# MeteoV4_0.net
KiCad netlist of a schematic drawn in EAGLE
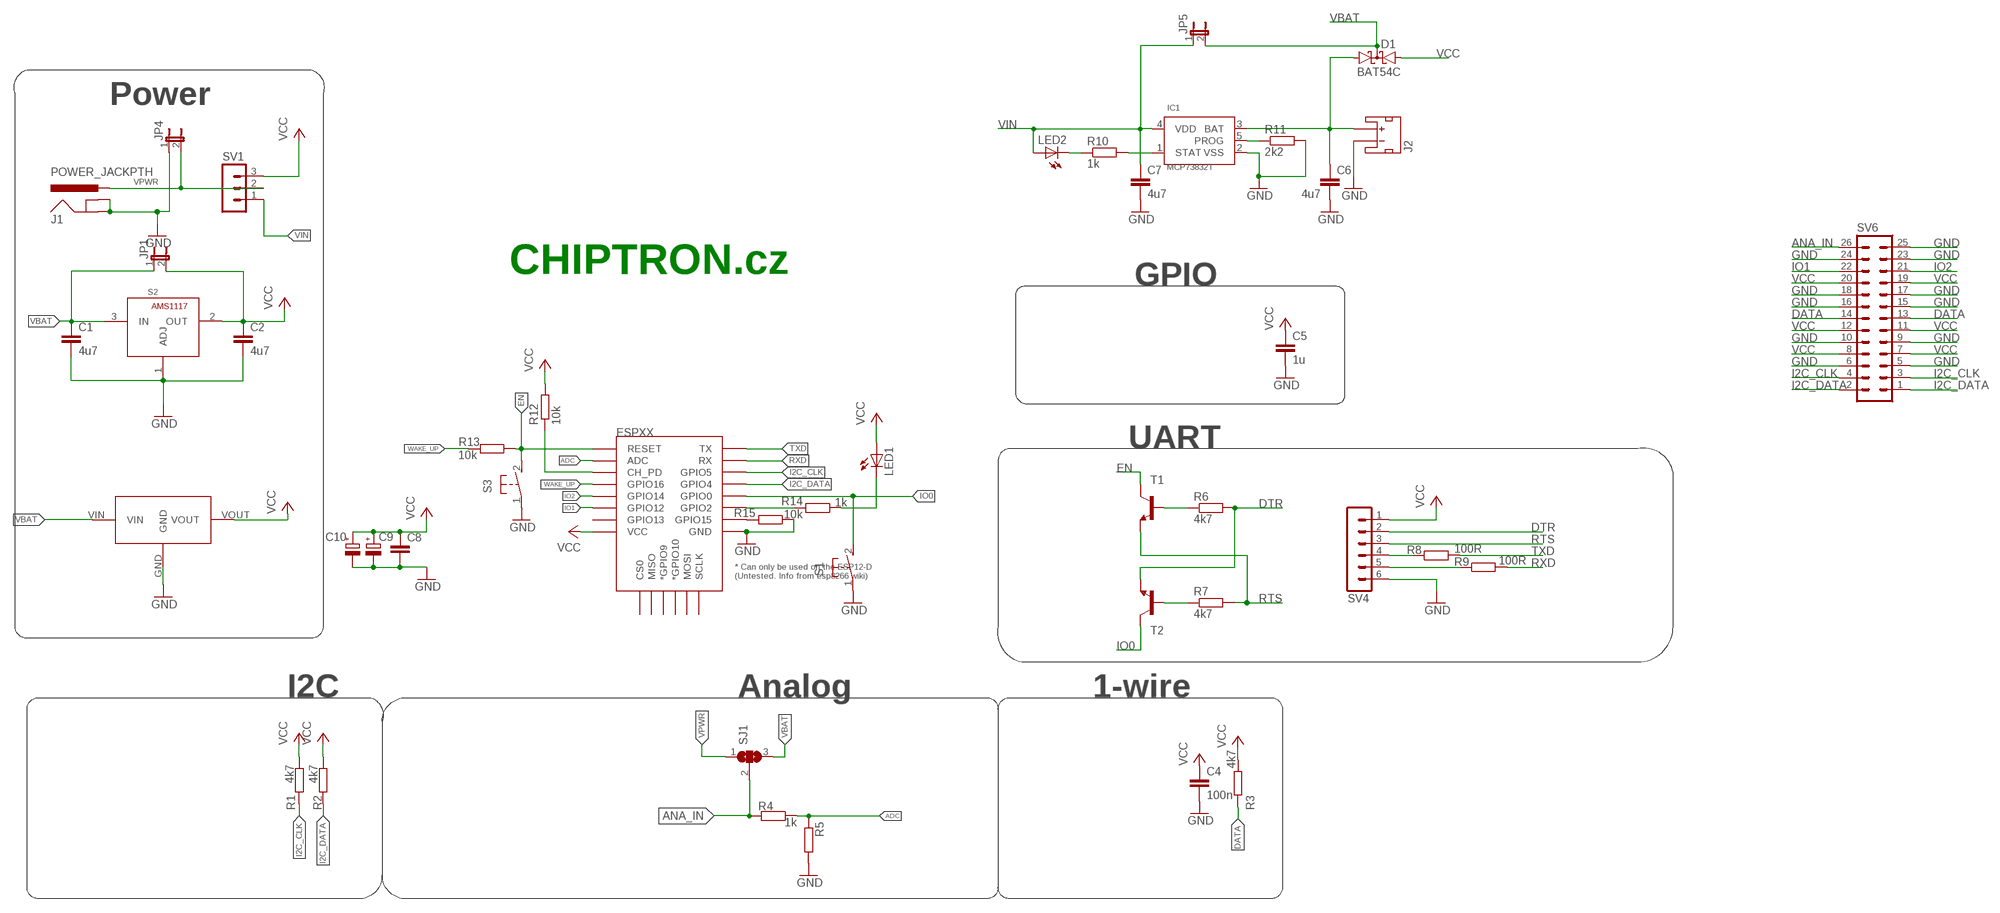
[diagram p0: schematic, sheet 1]

(export (version "E")
  (design (tool "Eeschema 10.0.6"))
  (components
    (comp (ref "C1")
      (value "4u7")
      (footprint "eagle-import:C0805")
      (libsource (lib "eagle-import") (part "C-EUC0805"))
    )
    (comp (ref "C2")
      (value "4u7")
      (footprint "eagle-import:C0805")
      (libsource (lib "eagle-import") (part "C-EUC0805"))
    )
    (comp (ref "C4")
      (value "100n")
      (footprint "eagle-import:C0805")
      (libsource (lib "eagle-import") (part "C-EUC0805"))
    )
    (comp (ref "C5")
      (value "1u")
      (footprint "eagle-import:C0805")
      (libsource (lib "eagle-import") (part "C-EUC0805"))
    )
    (comp (ref "C6")
      (value "4u7")
      (footprint "eagle-import:C0805")
      (libsource (lib "eagle-import") (part "C-EUC0805"))
    )
    (comp (ref "C7")
      (value "4u7")
      (footprint "eagle-import:C0805")
      (libsource (lib "eagle-import") (part "C-EUC0805"))
    )
    (comp (ref "C8")
      (value "C-EUC0805")
      (footprint "eagle-import:C0805")
      (libsource (lib "eagle-import") (part "C-EUC0805"))
    )
    (comp (ref "C9")
      (value "CPOL-EUSMCB")
      (footprint "eagle-import:SMC_B")
      (libsource (lib "eagle-import") (part "CPOL-EUSMCB"))
    )
    (comp (ref "C10")
      (value "CPOL-EUSMCC")
      (footprint "eagle-import:SMC_C")
      (libsource (lib "eagle-import") (part "CPOL-EUSMCC"))
    )
    (comp (ref "D1")
      (value "BAT54C")
      (footprint "eagle-import:SOT23")
      (libsource (lib "eagle-import") (part "BAT54C"))
    )
    (comp (ref "ESPXX")
      (value "ESP12ESMD")
      (footprint "eagle-import:ESP12E-SMD")
      (libsource (lib "eagle-import") (part "ESP12ESMD"))
    )
    (comp (ref "IC1")
      (value "MCP73832T")
      (footprint "eagle-import:SOT23-5")
      (libsource (lib "eagle-import") (part "MCP73832T"))
    )
    (comp (ref "J1")
      (value "POWER_JACKPTH")
      (footprint "eagle-import:POWER_JACK_PTH")
      (libsource (lib "eagle-import") (part "POWER_JACKPTH"))
    )
    (comp (ref "J2")
      (value "JST_2MM_MALE")
      (footprint "eagle-import:JST-2-SMD")
      (libsource (lib "eagle-import") (part "JST_2MM_MALE"))
    )
    (comp (ref "JP1")
      (value "JP1E")
      (footprint "eagle-import:JP1")
      (libsource (lib "eagle-import") (part "JP1E"))
    )
    (comp (ref "JP4")
      (value "JP1E")
      (footprint "eagle-import:JP1")
      (libsource (lib "eagle-import") (part "JP1E"))
    )
    (comp (ref "JP5")
      (value "JP1E")
      (footprint "eagle-import:JP1")
      (libsource (lib "eagle-import") (part "JP1E"))
    )
    (comp (ref "LED1")
      (value "LEDCHIP-LED0805")
      (footprint "eagle-import:CHIP-LED0805")
      (libsource (lib "eagle-import") (part "LEDCHIP-LED0805"))
    )
    (comp (ref "LED2")
      (value "LEDCHIP-LED0805")
      (footprint "eagle-import:CHIP-LED0805")
      (libsource (lib "eagle-import") (part "LEDCHIP-LED0805"))
    )
    (comp (ref "R1")
      (value "4k7")
      (footprint "eagle-import:M0805")
      (libsource (lib "eagle-import") (part "R-EU_M0805"))
    )
    (comp (ref "R2")
      (value "4k7")
      (footprint "eagle-import:M0805")
      (libsource (lib "eagle-import") (part "R-EU_M0805"))
    )
    (comp (ref "R3")
      (value "4k7")
      (footprint "eagle-import:M0805")
      (libsource (lib "eagle-import") (part "R-EU_M0805"))
    )
    (comp (ref "R4")
      (value "1k")
      (footprint "eagle-import:M0805")
      (libsource (lib "eagle-import") (part "R-EU_M0805"))
    )
    (comp (ref "R5")
      (value "R-EU_M0805")
      (footprint "eagle-import:M0805")
      (libsource (lib "eagle-import") (part "R-EU_M0805"))
    )
    (comp (ref "R6")
      (value "4k7")
      (footprint "eagle-import:M0805")
      (libsource (lib "eagle-import") (part "R-EU_M0805"))
    )
    (comp (ref "R7")
      (value "4k7")
      (footprint "eagle-import:M0805")
      (libsource (lib "eagle-import") (part "R-EU_M0805"))
    )
    (comp (ref "R8")
      (value "100R")
      (footprint "eagle-import:M0805")
      (libsource (lib "eagle-import") (part "R-EU_M0805"))
    )
    (comp (ref "R9")
      (value "100R")
      (footprint "eagle-import:M0805")
      (libsource (lib "eagle-import") (part "R-EU_M0805"))
    )
    (comp (ref "R10")
      (value "1k")
      (footprint "eagle-import:M0805")
      (libsource (lib "eagle-import") (part "R-EU_M0805"))
    )
    (comp (ref "R11")
      (value "2k2")
      (footprint "eagle-import:M0805")
      (libsource (lib "eagle-import") (part "R-EU_M0805"))
    )
    (comp (ref "R12")
      (value "10k")
      (footprint "eagle-import:M0805")
      (libsource (lib "eagle-import") (part "R-EU_M0805"))
    )
    (comp (ref "R13")
      (value "10k")
      (footprint "eagle-import:M0805")
      (libsource (lib "eagle-import") (part "R-EU_M0805"))
    )
    (comp (ref "R14")
      (value "1k")
      (footprint "eagle-import:M0805")
      (libsource (lib "eagle-import") (part "R-EU_M0805"))
    )
    (comp (ref "R15")
      (value "10k")
      (footprint "eagle-import:M0805")
      (libsource (lib "eagle-import") (part "R-EU_M0805"))
    )
    (comp (ref "S1")
      (value "31-XX")
      (footprint "eagle-import:B3F-31XX")
      (fields (field (name "MPN") "B3F-3100"))
      (libsource (lib "eagle-import") (part "31-XX"))
    )
    (comp (ref "S2")
      (value "AMS1117")
      (footprint "eagle-import:SOT-223-3")
      (libsource (lib "eagle-import") (part "AMS1117"))
    )
    (comp (ref "S3")
      (value "31-XX")
      (footprint "eagle-import:B3F-31XX")
      (fields (field (name "MPN") "B3F-3100"))
      (libsource (lib "eagle-import") (part "31-XX"))
    )
    (comp (ref "SJ1")
      (value "SJ2W")
      (footprint "eagle-import:SJ_2")
      (libsource (lib "eagle-import") (part "SJ2W"))
    )
    (comp (ref "SV1")
      (value "MA03-1")
      (footprint "eagle-import:MA03-1")
      (libsource (lib "eagle-import") (part "MA03-1"))
    )
    (comp (ref "SV4")
      (value "MA06-1")
      (footprint "eagle-import:MA06-1")
      (libsource (lib "eagle-import") (part "MA06-1"))
    )
    (comp (ref "SV6")
      (value "MA13-2")
      (footprint "eagle-import:MA13-2")
      (libsource (lib "eagle-import") (part "MA13-2"))
    )
    (comp (ref "T1")
      (value "BC846-NPN-SOT23-BEC")
      (footprint "eagle-import:SOT23-BEC")
      (libsource (lib "eagle-import") (part "-NPN-SOT23-BECBC846"))
    )
    (comp (ref "T2")
      (value "BC846-NPN-SOT23-BEC")
      (footprint "eagle-import:SOT23-BEC")
      (libsource (lib "eagle-import") (part "-NPN-SOT23-BECBC846"))
    )
    (comp (ref "U$1")
      (value "HT7333")
      (footprint "eagle-import:SOT89")
      (libsource (lib "eagle-import") (part "HT7333"))
    )
  )
  (nets
    (net (code "1") (name "/DTR") (class "Default")
      (node (ref "R6") (pin "2") (pinfunction "2_2") (pintype "passive"))
      (node (ref "SV4") (pin "2") (pinfunction "2_2") (pintype "passive"))
      (node (ref "T2") (pin "E") (pinfunction "E_E") (pintype "passive"))
    )
    (net (code "2") (name "/RTS") (class "Default")
      (node (ref "R7") (pin "2") (pinfunction "2_2") (pintype "passive"))
      (node (ref "SV4") (pin "3") (pinfunction "3_3") (pintype "passive"))
      (node (ref "T1") (pin "E") (pinfunction "E_E") (pintype "passive"))
    )
    (net (code "3") (name "ADC") (class "Default")
      (node (ref "ESPXX") (pin "ADC") (pinfunction "ADC_ADC") (pintype "bidirectional"))
      (node (ref "R4") (pin "1") (pinfunction "1_1") (pintype "passive"))
      (node (ref "R5") (pin "1") (pinfunction "1_1") (pintype "passive"))
    )
    (net (code "4") (name "ANA_IN") (class "Default")
      (node (ref "R4") (pin "2") (pinfunction "2_2") (pintype "passive"))
      (node (ref "SJ1") (pin "2") (pinfunction "2_2") (pintype "passive"))
      (node (ref "SV6") (pin "26") (pinfunction "26_26") (pintype "passive"))
    )
    (net (code "5") (name "DATA") (class "Default")
      (node (ref "R3") (pin "1") (pinfunction "1_1") (pintype "passive"))
      (node (ref "SV6") (pin "13") (pinfunction "13_13") (pintype "passive"))
      (node (ref "SV6") (pin "14") (pinfunction "14_14") (pintype "passive"))
    )
    (net (code "6") (name "EN") (class "Default")
      (node (ref "ESPXX") (pin "RESET") (pinfunction "RESET_RESET") (pintype "bidirectional"))
      (node (ref "R13") (pin "1") (pinfunction "1_1") (pintype "passive"))
      (node (ref "S3") (pin "2") (pinfunction "S_2") (pintype "passive"))
      (node (ref "T1") (pin "C") (pinfunction "C_C") (pintype "passive"))
    )
    (net (code "7") (name "GND") (class "Default")
      (node (ref "C1") (pin "2") (pinfunction "2_2") (pintype "passive"))
      (node (ref "C10") (pin "-") (pinfunction "-_-") (pintype "passive"))
      (node (ref "C2") (pin "2") (pinfunction "2_2") (pintype "passive"))
      (node (ref "C4") (pin "2") (pinfunction "2_2") (pintype "passive"))
      (node (ref "C5") (pin "2") (pinfunction "2_2") (pintype "passive"))
      (node (ref "C6") (pin "2") (pinfunction "2_2") (pintype "passive"))
      (node (ref "C7") (pin "2") (pinfunction "2_2") (pintype "passive"))
      (node (ref "C8") (pin "2") (pinfunction "2_2") (pintype "passive"))
      (node (ref "C9") (pin "-") (pinfunction "-_-") (pintype "passive"))
      (node (ref "ESPXX") (pin "GND") (pinfunction "GND_GND") (pintype "bidirectional"))
      (node (ref "IC1") (pin "2") (pinfunction "VSS_2") (pintype "bidirectional"))
      (node (ref "J1") (pin "GND") (pinfunction "GND_GND") (pintype "bidirectional"))
      (node (ref "J1") (pin "GNDBREAK") (pinfunction "GNDBREAK_GNDBREAK") (pintype "bidirectional"))
      (node (ref "J2") (pin "1") (pinfunction "-_1") (pintype "bidirectional"))
      (node (ref "JP4") (pin "1") (pinfunction "1_1") (pintype "passive"))
      (node (ref "R11") (pin "2") (pinfunction "2_2") (pintype "passive"))
      (node (ref "R15") (pin "1") (pinfunction "1_1") (pintype "passive"))
      (node (ref "R5") (pin "2") (pinfunction "2_2") (pintype "passive"))
      (node (ref "S1") (pin "1") (pinfunction "P_1") (pintype "passive"))
      (node (ref "S2") (pin "1") (pinfunction "ADJ_1") (pintype "bidirectional"))
      (node (ref "S3") (pin "1") (pinfunction "P_1") (pintype "passive"))
      (node (ref "SV4") (pin "6") (pinfunction "6_6") (pintype "passive"))
      (node (ref "SV6") (pin "10") (pinfunction "10_10") (pintype "passive"))
      (node (ref "SV6") (pin "15") (pinfunction "15_15") (pintype "passive"))
      (node (ref "SV6") (pin "16") (pinfunction "16_16") (pintype "passive"))
      (node (ref "SV6") (pin "17") (pinfunction "17_17") (pintype "passive"))
      (node (ref "SV6") (pin "18") (pinfunction "18_18") (pintype "passive"))
      (node (ref "SV6") (pin "23") (pinfunction "23_23") (pintype "passive"))
      (node (ref "SV6") (pin "24") (pinfunction "24_24") (pintype "passive"))
      (node (ref "SV6") (pin "25") (pinfunction "25_25") (pintype "passive"))
      (node (ref "SV6") (pin "5") (pinfunction "5_5") (pintype "passive"))
      (node (ref "SV6") (pin "6") (pinfunction "6_6") (pintype "passive"))
      (node (ref "SV6") (pin "9") (pinfunction "9_9") (pintype "passive"))
      (node (ref "U$1") (pin "GND") (pinfunction "GND_GND") (pintype "bidirectional"))
    )
    (net (code "8") (name "I2C_CLK") (class "Default")
      (node (ref "ESPXX") (pin "GPIO5") (pinfunction "GPIO5_GPIO5") (pintype "bidirectional"))
      (node (ref "R1") (pin "1") (pinfunction "1_1") (pintype "passive"))
      (node (ref "SV6") (pin "3") (pinfunction "3_3") (pintype "passive"))
      (node (ref "SV6") (pin "4") (pinfunction "4_4") (pintype "passive"))
    )
    (net (code "9") (name "I2C_DATA") (class "Default")
      (node (ref "ESPXX") (pin "GPIO4") (pinfunction "GPIO4_GPIO4") (pintype "bidirectional"))
      (node (ref "R2") (pin "1") (pinfunction "1_1") (pintype "passive"))
      (node (ref "SV6") (pin "1") (pinfunction "1_1") (pintype "passive"))
      (node (ref "SV6") (pin "2") (pinfunction "2_2") (pintype "passive"))
    )
    (net (code "10") (name "IO0") (class "Default")
      (node (ref "ESPXX") (pin "GPIO0") (pinfunction "GPIO0_GPIO0") (pintype "bidirectional"))
      (node (ref "S1") (pin "2") (pinfunction "S_2") (pintype "passive"))
      (node (ref "T2") (pin "C") (pinfunction "C_C") (pintype "passive"))
    )
    (net (code "11") (name "IO1") (class "Default")
      (node (ref "ESPXX") (pin "GPIO12") (pinfunction "GPIO12_GPIO12") (pintype "bidirectional"))
      (node (ref "SV6") (pin "22") (pinfunction "22_22") (pintype "passive"))
    )
    (net (code "12") (name "IO2") (class "Default")
      (node (ref "ESPXX") (pin "GPIO14") (pinfunction "GPIO14_GPIO14") (pintype "bidirectional"))
      (node (ref "SV6") (pin "21") (pinfunction "21_21") (pintype "passive"))
    )
    (net (code "13") (name "Net-(D1-A1)") (class "Default")
      (node (ref "C6") (pin "1") (pinfunction "1_1") (pintype "passive"))
      (node (ref "D1") (pin "1") (pinfunction "A1_1") (pintype "passive"))
      (node (ref "IC1") (pin "3") (pinfunction "BAT_3") (pintype "bidirectional"))
      (node (ref "J2") (pin "2") (pinfunction "+_2") (pintype "bidirectional"))
    )
    (net (code "14") (name "Net-(ESPXX-PadCH_PD)") (class "Default")
      (node (ref "ESPXX") (pin "CH_PD") (pinfunction "CH_PD_CH_PD") (pintype "bidirectional"))
      (node (ref "R12") (pin "1") (pinfunction "1_1") (pintype "passive"))
    )
    (net (code "15") (name "Net-(ESPXX-PadGPIO2)") (class "Default")
      (node (ref "ESPXX") (pin "GPIO2") (pinfunction "GPIO2_GPIO2") (pintype "bidirectional"))
      (node (ref "R14") (pin "2") (pinfunction "2_2") (pintype "passive"))
    )
    (net (code "16") (name "Net-(ESPXX-PadGPIO15)") (class "Default")
      (node (ref "ESPXX") (pin "GPIO15") (pinfunction "GPIO15_GPIO15") (pintype "bidirectional"))
      (node (ref "R15") (pin "2") (pinfunction "2_2") (pintype "passive"))
    )
    (net (code "17") (name "Net-(IC1-PROG)") (class "Default")
      (node (ref "IC1") (pin "5") (pinfunction "PROG_5") (pintype "bidirectional"))
      (node (ref "R11") (pin "1") (pinfunction "1_1") (pintype "passive"))
    )
    (net (code "18") (name "Net-(IC1-STAT)") (class "Default")
      (node (ref "IC1") (pin "1") (pinfunction "STAT_1") (pintype "bidirectional"))
      (node (ref "R10") (pin "2") (pinfunction "2_2") (pintype "passive"))
    )
    (net (code "19") (name "Net-(LED1-PadC)") (class "Default")
      (node (ref "LED1") (pin "C") (pinfunction "C_C") (pintype "passive"))
      (node (ref "R14") (pin "1") (pinfunction "1_1") (pintype "passive"))
    )
    (net (code "20") (name "Net-(LED2-PadC)") (class "Default")
      (node (ref "LED2") (pin "C") (pinfunction "C_C") (pintype "passive"))
      (node (ref "R10") (pin "1") (pinfunction "1_1") (pintype "passive"))
    )
    (net (code "21") (name "Net-(R6-Pad1)") (class "Default")
      (node (ref "R6") (pin "1") (pinfunction "1_1") (pintype "passive"))
      (node (ref "T1") (pin "B") (pinfunction "B_B") (pintype "passive"))
    )
    (net (code "22") (name "Net-(R7-Pad1)") (class "Default")
      (node (ref "R7") (pin "1") (pinfunction "1_1") (pintype "passive"))
      (node (ref "T2") (pin "B") (pinfunction "B_B") (pintype "passive"))
    )
    (net (code "23") (name "Net-(R8-Pad1)") (class "Default")
      (node (ref "R8") (pin "1") (pinfunction "1_1") (pintype "passive"))
      (node (ref "SV4") (pin "4") (pinfunction "4_4") (pintype "passive"))
    )
    (net (code "24") (name "Net-(R9-Pad1)") (class "Default")
      (node (ref "R9") (pin "1") (pinfunction "1_1") (pintype "passive"))
      (node (ref "SV4") (pin "5") (pinfunction "5_5") (pintype "passive"))
    )
    (net (code "25") (name "RXD") (class "Default")
      (node (ref "ESPXX") (pin "RXD0") (pinfunction "RX_RXD0") (pintype "bidirectional"))
      (node (ref "R9") (pin "2") (pinfunction "2_2") (pintype "passive"))
    )
    (net (code "26") (name "TXD") (class "Default")
      (node (ref "ESPXX") (pin "TXD0") (pinfunction "TX_TXD0") (pintype "bidirectional"))
      (node (ref "R8") (pin "2") (pinfunction "2_2") (pintype "passive"))
    )
    (net (code "27") (name "VBAT") (class "Default")
      (node (ref "C1") (pin "1") (pinfunction "1_1") (pintype "passive"))
      (node (ref "D1") (pin "3") (pinfunction "CC_3") (pintype "passive"))
      (node (ref "JP1") (pin "1") (pinfunction "1_1") (pintype "passive"))
      (node (ref "JP5") (pin "2") (pinfunction "2_2") (pintype "passive"))
      (node (ref "S2") (pin "3") (pinfunction "IN_3") (pintype "bidirectional"))
      (node (ref "SJ1") (pin "3") (pinfunction "3_3") (pintype "passive"))
      (node (ref "U$1") (pin "VIN") (pinfunction "VIN_VIN") (pintype "bidirectional"))
    )
    (net (code "28") (name "VCC") (class "Default")
      (node (ref "C10") (pin "+") (pinfunction "+_+") (pintype "passive"))
      (node (ref "C2") (pin "1") (pinfunction "1_1") (pintype "passive"))
      (node (ref "C4") (pin "1") (pinfunction "1_1") (pintype "passive"))
      (node (ref "C5") (pin "1") (pinfunction "1_1") (pintype "passive"))
      (node (ref "C8") (pin "1") (pinfunction "1_1") (pintype "passive"))
      (node (ref "C9") (pin "+") (pinfunction "+_+") (pintype "passive"))
      (node (ref "D1") (pin "2") (pinfunction "A2_2") (pintype "passive"))
      (node (ref "ESPXX") (pin "VCC") (pinfunction "VCC_VCC") (pintype "bidirectional"))
      (node (ref "JP1") (pin "2") (pinfunction "2_2") (pintype "passive"))
      (node (ref "LED1") (pin "A") (pinfunction "A_A") (pintype "passive"))
      (node (ref "R1") (pin "2") (pinfunction "2_2") (pintype "passive"))
      (node (ref "R12") (pin "2") (pinfunction "2_2") (pintype "passive"))
      (node (ref "R2") (pin "2") (pinfunction "2_2") (pintype "passive"))
      (node (ref "R3") (pin "2") (pinfunction "2_2") (pintype "passive"))
      (node (ref "S2") (pin "2") (pinfunction "OUT_2") (pintype "bidirectional"))
      (node (ref "SV1") (pin "3") (pinfunction "3_3") (pintype "passive"))
      (node (ref "SV4") (pin "1") (pinfunction "1_1") (pintype "passive"))
      (node (ref "SV6") (pin "11") (pinfunction "11_11") (pintype "passive"))
      (node (ref "SV6") (pin "12") (pinfunction "12_12") (pintype "passive"))
      (node (ref "SV6") (pin "19") (pinfunction "19_19") (pintype "passive"))
      (node (ref "SV6") (pin "20") (pinfunction "20_20") (pintype "passive"))
      (node (ref "SV6") (pin "7") (pinfunction "7_7") (pintype "passive"))
      (node (ref "SV6") (pin "8") (pinfunction "8_8") (pintype "passive"))
      (node (ref "U$1") (pin "VOUT") (pinfunction "VOUT_VOUT") (pintype "bidirectional"))
    )
    (net (code "29") (name "VIN") (class "Default")
      (node (ref "C7") (pin "1") (pinfunction "1_1") (pintype "passive"))
      (node (ref "IC1") (pin "4") (pinfunction "VDD_4") (pintype "bidirectional"))
      (node (ref "JP5") (pin "1") (pinfunction "1_1") (pintype "passive"))
      (node (ref "LED2") (pin "A") (pinfunction "A_A") (pintype "passive"))
      (node (ref "SV1") (pin "1") (pinfunction "1_1") (pintype "passive"))
    )
    (net (code "30") (name "VPWR") (class "Default")
      (node (ref "J1") (pin "PWR") (pinfunction "PWR_PWR") (pintype "bidirectional"))
      (node (ref "JP4") (pin "2") (pinfunction "2_2") (pintype "passive"))
      (node (ref "SJ1") (pin "1") (pinfunction "1_1") (pintype "passive"))
      (node (ref "SV1") (pin "2") (pinfunction "2_2") (pintype "passive"))
    )
    (net (code "31") (name "WAKE_UP") (class "Default")
      (node (ref "ESPXX") (pin "GPIO16") (pinfunction "GPIO16_GPIO16") (pintype "bidirectional"))
      (node (ref "R13") (pin "2") (pinfunction "2_2") (pintype "passive"))
    )
    (net (code "32") (name "unconnected-(ESPXX-*GPIO9-PadGPIO9)") (class "Default")
      (node (ref "ESPXX") (pin "GPIO9") (pinfunction "*GPIO9_GPIO9") (pintype "bidirectional"))
    )
    (net (code "33") (name "unconnected-(ESPXX-*GPIO10-PadGPIO10)") (class "Default")
      (node (ref "ESPXX") (pin "GPIO10") (pinfunction "*GPIO10_GPIO10") (pintype "bidirectional"))
    )
    (net (code "34") (name "unconnected-(ESPXX-PadCS0)") (class "Default")
      (node (ref "ESPXX") (pin "CS0") (pinfunction "CS0_CS0") (pintype "bidirectional"))
    )
    (net (code "35") (name "unconnected-(ESPXX-PadGPIO13)") (class "Default")
      (node (ref "ESPXX") (pin "GPIO13") (pinfunction "GPIO13_GPIO13") (pintype "bidirectional"))
    )
    (net (code "36") (name "unconnected-(ESPXX-PadMISO)") (class "Default")
      (node (ref "ESPXX") (pin "MISO") (pinfunction "MISO_MISO") (pintype "bidirectional"))
    )
    (net (code "37") (name "unconnected-(ESPXX-PadMOSI)") (class "Default")
      (node (ref "ESPXX") (pin "MOSI") (pinfunction "MOSI_MOSI") (pintype "bidirectional"))
    )
    (net (code "38") (name "unconnected-(ESPXX-PadSCLK)") (class "Default")
      (node (ref "ESPXX") (pin "SCLK") (pinfunction "SCLK_SCLK") (pintype "bidirectional"))
    )
    (net (code "39") (name "unconnected-(J2-PAD1-PadNC1)") (class "Default")
      (node (ref "J2") (pin "NC1") (pinfunction "PAD1_NC1") (pintype "bidirectional"))
    )
    (net (code "40") (name "unconnected-(J2-PAD2-PadNC2)") (class "Default")
      (node (ref "J2") (pin "NC2") (pinfunction "PAD2_NC2") (pintype "bidirectional"))
    )
  )
)
